# 02_-_TRICOLOR_LEDS.net
KiCad netlist of a schematic drawn in Altium Designer
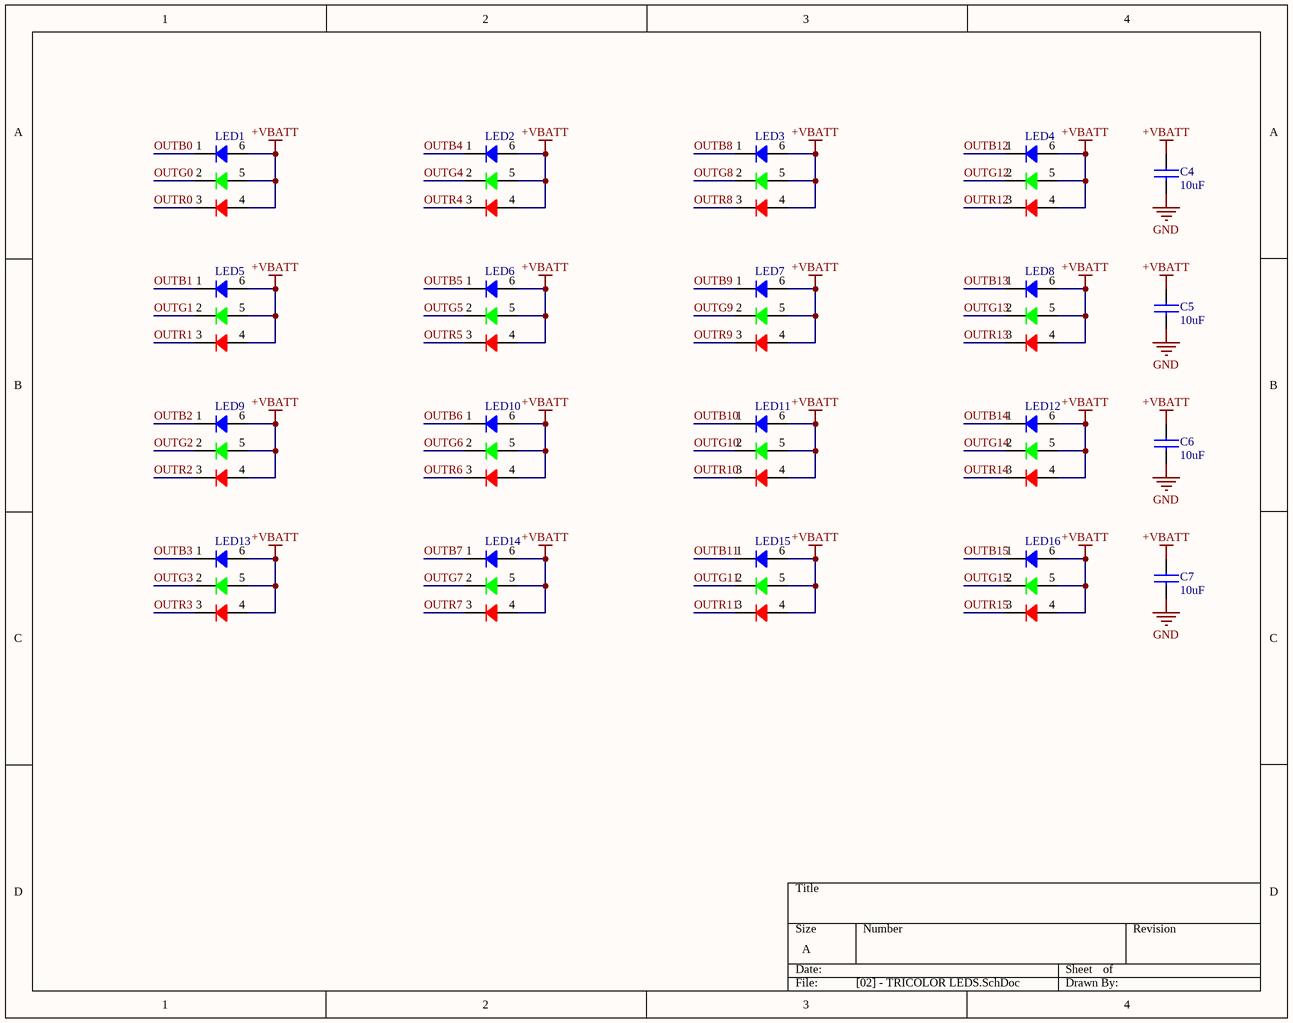
[diagram p0: [02] - TRICOLOR LEDS.SchDoc]

(export (version "E")
  (design (tool "Eeschema 10.0.6"))
  (components
    (comp (ref "C4")
      (value "10uF")
      (footprint "C0603")
      (description "Cap Ceramic 10uF 10V X5R 10% SMD 0603 85C Paper T/R")
      (fields (field (name "MANUFACTURER") "Murata") (field (name "TOLERANCE") "10%"))
      (libsource (lib "Moon_Lamp_LED_Driver") (part "GRM188R61A106KE69D"))
    )
    (comp (ref "C5")
      (value "10uF")
      (footprint "C0603")
      (description "Cap Ceramic 10uF 10V X5R 10% SMD 0603 85C Paper T/R")
      (fields (field (name "MANUFACTURER") "Murata") (field (name "TOLERANCE") "10%"))
      (libsource (lib "Moon_Lamp_LED_Driver") (part "GRM188R61A106KE69D"))
    )
    (comp (ref "C6")
      (value "10uF")
      (footprint "C0603")
      (description "Cap Ceramic 10uF 10V X5R 10% SMD 0603 85C Paper T/R")
      (fields (field (name "MANUFACTURER") "Murata") (field (name "TOLERANCE") "10%"))
      (libsource (lib "Moon_Lamp_LED_Driver") (part "GRM188R61A106KE69D"))
    )
    (comp (ref "C7")
      (value "10uF")
      (footprint "C0603")
      (description "Cap Ceramic 10uF 10V X5R 10% SMD 0603 85C Paper T/R")
      (fields (field (name "MANUFACTURER") "Murata") (field (name "TOLERANCE") "10%"))
      (libsource (lib "Moon_Lamp_LED_Driver") (part "GRM188R61A106KE69D"))
    )
    (comp (ref "LED1")
      (value "SLV6A-FKB-CK1P1G1BB7R3R3")
      (footprint "CREE SLV6A-FKB")
      (description "LED RGB 6PLCC SMD")
      (fields (field (name "MANUFACTURER") "Cree"))
      (libsource (lib "Moon_Lamp_LED_Driver") (part "SLV6A-FKB-CK1P1G1BB7R3R3"))
    )
    (comp (ref "LED2")
      (value "SLV6A-FKB-CK1P1G1BB7R3R3")
      (footprint "CREE SLV6A-FKB")
      (description "LED RGB 6PLCC SMD")
      (fields (field (name "MANUFACTURER") "Cree"))
      (libsource (lib "Moon_Lamp_LED_Driver") (part "SLV6A-FKB-CK1P1G1BB7R3R3"))
    )
    (comp (ref "LED3")
      (value "SLV6A-FKB-CK1P1G1BB7R3R3")
      (footprint "CREE SLV6A-FKB")
      (description "LED RGB 6PLCC SMD")
      (fields (field (name "MANUFACTURER") "Cree"))
      (libsource (lib "Moon_Lamp_LED_Driver") (part "SLV6A-FKB-CK1P1G1BB7R3R3"))
    )
    (comp (ref "LED4")
      (value "SLV6A-FKB-CK1P1G1BB7R3R3")
      (footprint "CREE SLV6A-FKB")
      (description "LED RGB 6PLCC SMD")
      (fields (field (name "MANUFACTURER") "Cree"))
      (libsource (lib "Moon_Lamp_LED_Driver") (part "SLV6A-FKB-CK1P1G1BB7R3R3"))
    )
    (comp (ref "LED5")
      (value "SLV6A-FKB-CK1P1G1BB7R3R3")
      (footprint "CREE SLV6A-FKB")
      (description "LED RGB 6PLCC SMD")
      (fields (field (name "MANUFACTURER") "Cree"))
      (libsource (lib "Moon_Lamp_LED_Driver") (part "SLV6A-FKB-CK1P1G1BB7R3R3"))
    )
    (comp (ref "LED6")
      (value "SLV6A-FKB-CK1P1G1BB7R3R3")
      (footprint "CREE SLV6A-FKB")
      (description "LED RGB 6PLCC SMD")
      (fields (field (name "MANUFACTURER") "Cree"))
      (libsource (lib "Moon_Lamp_LED_Driver") (part "SLV6A-FKB-CK1P1G1BB7R3R3"))
    )
    (comp (ref "LED7")
      (value "SLV6A-FKB-CK1P1G1BB7R3R3")
      (footprint "CREE SLV6A-FKB")
      (description "LED RGB 6PLCC SMD")
      (fields (field (name "MANUFACTURER") "Cree"))
      (libsource (lib "Moon_Lamp_LED_Driver") (part "SLV6A-FKB-CK1P1G1BB7R3R3"))
    )
    (comp (ref "LED8")
      (value "SLV6A-FKB-CK1P1G1BB7R3R3")
      (footprint "CREE SLV6A-FKB")
      (description "LED RGB 6PLCC SMD")
      (fields (field (name "MANUFACTURER") "Cree"))
      (libsource (lib "Moon_Lamp_LED_Driver") (part "SLV6A-FKB-CK1P1G1BB7R3R3"))
    )
    (comp (ref "LED9")
      (value "SLV6A-FKB-CK1P1G1BB7R3R3")
      (footprint "CREE SLV6A-FKB")
      (description "LED RGB 6PLCC SMD")
      (fields (field (name "MANUFACTURER") "Cree"))
      (libsource (lib "Moon_Lamp_LED_Driver") (part "SLV6A-FKB-CK1P1G1BB7R3R3"))
    )
    (comp (ref "LED10")
      (value "SLV6A-FKB-CK1P1G1BB7R3R3")
      (footprint "CREE SLV6A-FKB")
      (description "LED RGB 6PLCC SMD")
      (fields (field (name "MANUFACTURER") "Cree"))
      (libsource (lib "Moon_Lamp_LED_Driver") (part "SLV6A-FKB-CK1P1G1BB7R3R3"))
    )
    (comp (ref "LED11")
      (value "SLV6A-FKB-CK1P1G1BB7R3R3")
      (footprint "CREE SLV6A-FKB")
      (description "LED RGB 6PLCC SMD")
      (fields (field (name "MANUFACTURER") "Cree"))
      (libsource (lib "Moon_Lamp_LED_Driver") (part "SLV6A-FKB-CK1P1G1BB7R3R3"))
    )
    (comp (ref "LED12")
      (value "SLV6A-FKB-CK1P1G1BB7R3R3")
      (footprint "CREE SLV6A-FKB")
      (description "LED RGB 6PLCC SMD")
      (fields (field (name "MANUFACTURER") "Cree"))
      (libsource (lib "Moon_Lamp_LED_Driver") (part "SLV6A-FKB-CK1P1G1BB7R3R3"))
    )
    (comp (ref "LED13")
      (value "SLV6A-FKB-CK1P1G1BB7R3R3")
      (footprint "CREE SLV6A-FKB")
      (description "LED RGB 6PLCC SMD")
      (fields (field (name "MANUFACTURER") "Cree"))
      (libsource (lib "Moon_Lamp_LED_Driver") (part "SLV6A-FKB-CK1P1G1BB7R3R3"))
    )
    (comp (ref "LED14")
      (value "SLV6A-FKB-CK1P1G1BB7R3R3")
      (footprint "CREE SLV6A-FKB")
      (description "LED RGB 6PLCC SMD")
      (fields (field (name "MANUFACTURER") "Cree"))
      (libsource (lib "Moon_Lamp_LED_Driver") (part "SLV6A-FKB-CK1P1G1BB7R3R3"))
    )
    (comp (ref "LED15")
      (value "SLV6A-FKB-CK1P1G1BB7R3R3")
      (footprint "CREE SLV6A-FKB")
      (description "LED RGB 6PLCC SMD")
      (fields (field (name "MANUFACTURER") "Cree"))
      (libsource (lib "Moon_Lamp_LED_Driver") (part "SLV6A-FKB-CK1P1G1BB7R3R3"))
    )
    (comp (ref "LED16")
      (value "SLV6A-FKB-CK1P1G1BB7R3R3")
      (footprint "CREE SLV6A-FKB")
      (description "LED RGB 6PLCC SMD")
      (fields (field (name "MANUFACTURER") "Cree"))
      (libsource (lib "Moon_Lamp_LED_Driver") (part "SLV6A-FKB-CK1P1G1BB7R3R3"))
    )
  )
  (nets
    (net (code "1") (name "+VBATT") (class "Default")
      (node (ref "C4") (pin "1") (pinfunction "1_1") (pintype "passive"))
      (node (ref "C5") (pin "1") (pinfunction "1_1") (pintype "passive"))
      (node (ref "C6") (pin "1") (pinfunction "1_1") (pintype "passive"))
      (node (ref "C7") (pin "1") (pinfunction "1_1") (pintype "passive"))
      (node (ref "LED1") (pin "4") (pinfunction "4_4") (pintype "passive"))
      (node (ref "LED1") (pin "5") (pinfunction "5_5") (pintype "passive"))
      (node (ref "LED1") (pin "6") (pinfunction "6_6") (pintype "passive"))
      (node (ref "LED10") (pin "4") (pinfunction "4_4") (pintype "passive"))
      (node (ref "LED10") (pin "5") (pinfunction "5_5") (pintype "passive"))
      (node (ref "LED10") (pin "6") (pinfunction "6_6") (pintype "passive"))
      (node (ref "LED11") (pin "4") (pinfunction "4_4") (pintype "passive"))
      (node (ref "LED11") (pin "5") (pinfunction "5_5") (pintype "passive"))
      (node (ref "LED11") (pin "6") (pinfunction "6_6") (pintype "passive"))
      (node (ref "LED12") (pin "4") (pinfunction "4_4") (pintype "passive"))
      (node (ref "LED12") (pin "5") (pinfunction "5_5") (pintype "passive"))
      (node (ref "LED12") (pin "6") (pinfunction "6_6") (pintype "passive"))
      (node (ref "LED13") (pin "4") (pinfunction "4_4") (pintype "passive"))
      (node (ref "LED13") (pin "5") (pinfunction "5_5") (pintype "passive"))
      (node (ref "LED13") (pin "6") (pinfunction "6_6") (pintype "passive"))
      (node (ref "LED14") (pin "4") (pinfunction "4_4") (pintype "passive"))
      (node (ref "LED14") (pin "5") (pinfunction "5_5") (pintype "passive"))
      (node (ref "LED14") (pin "6") (pinfunction "6_6") (pintype "passive"))
      (node (ref "LED15") (pin "4") (pinfunction "4_4") (pintype "passive"))
      (node (ref "LED15") (pin "5") (pinfunction "5_5") (pintype "passive"))
      (node (ref "LED15") (pin "6") (pinfunction "6_6") (pintype "passive"))
      (node (ref "LED16") (pin "4") (pinfunction "4_4") (pintype "passive"))
      (node (ref "LED16") (pin "5") (pinfunction "5_5") (pintype "passive"))
      (node (ref "LED16") (pin "6") (pinfunction "6_6") (pintype "passive"))
      (node (ref "LED2") (pin "4") (pinfunction "4_4") (pintype "passive"))
      (node (ref "LED2") (pin "5") (pinfunction "5_5") (pintype "passive"))
      (node (ref "LED2") (pin "6") (pinfunction "6_6") (pintype "passive"))
      (node (ref "LED3") (pin "4") (pinfunction "4_4") (pintype "passive"))
      (node (ref "LED3") (pin "5") (pinfunction "5_5") (pintype "passive"))
      (node (ref "LED3") (pin "6") (pinfunction "6_6") (pintype "passive"))
      (node (ref "LED4") (pin "4") (pinfunction "4_4") (pintype "passive"))
      (node (ref "LED4") (pin "5") (pinfunction "5_5") (pintype "passive"))
      (node (ref "LED4") (pin "6") (pinfunction "6_6") (pintype "passive"))
      (node (ref "LED5") (pin "4") (pinfunction "4_4") (pintype "passive"))
      (node (ref "LED5") (pin "5") (pinfunction "5_5") (pintype "passive"))
      (node (ref "LED5") (pin "6") (pinfunction "6_6") (pintype "passive"))
      (node (ref "LED6") (pin "4") (pinfunction "4_4") (pintype "passive"))
      (node (ref "LED6") (pin "5") (pinfunction "5_5") (pintype "passive"))
      (node (ref "LED6") (pin "6") (pinfunction "6_6") (pintype "passive"))
      (node (ref "LED7") (pin "4") (pinfunction "4_4") (pintype "passive"))
      (node (ref "LED7") (pin "5") (pinfunction "5_5") (pintype "passive"))
      (node (ref "LED7") (pin "6") (pinfunction "6_6") (pintype "passive"))
      (node (ref "LED8") (pin "4") (pinfunction "4_4") (pintype "passive"))
      (node (ref "LED8") (pin "5") (pinfunction "5_5") (pintype "passive"))
      (node (ref "LED8") (pin "6") (pinfunction "6_6") (pintype "passive"))
      (node (ref "LED9") (pin "4") (pinfunction "4_4") (pintype "passive"))
      (node (ref "LED9") (pin "5") (pinfunction "5_5") (pintype "passive"))
      (node (ref "LED9") (pin "6") (pinfunction "6_6") (pintype "passive"))
    )
    (net (code "2") (name "/OUTB0") (class "Default")
      (node (ref "LED1") (pin "1") (pinfunction "1_1") (pintype "passive"))
    )
    (net (code "3") (name "/OUTB1") (class "Default")
      (node (ref "LED5") (pin "1") (pinfunction "1_1") (pintype "passive"))
    )
    (net (code "4") (name "/OUTB2") (class "Default")
      (node (ref "LED9") (pin "1") (pinfunction "1_1") (pintype "passive"))
    )
    (net (code "5") (name "/OUTB3") (class "Default")
      (node (ref "LED13") (pin "1") (pinfunction "1_1") (pintype "passive"))
    )
    (net (code "6") (name "/OUTB4") (class "Default")
      (node (ref "LED2") (pin "1") (pinfunction "1_1") (pintype "passive"))
    )
    (net (code "7") (name "/OUTB5") (class "Default")
      (node (ref "LED6") (pin "1") (pinfunction "1_1") (pintype "passive"))
    )
    (net (code "8") (name "/OUTB6") (class "Default")
      (node (ref "LED10") (pin "1") (pinfunction "1_1") (pintype "passive"))
    )
    (net (code "9") (name "/OUTB7") (class "Default")
      (node (ref "LED14") (pin "1") (pinfunction "1_1") (pintype "passive"))
    )
    (net (code "10") (name "/OUTB8") (class "Default")
      (node (ref "LED3") (pin "1") (pinfunction "1_1") (pintype "passive"))
    )
    (net (code "11") (name "/OUTB9") (class "Default")
      (node (ref "LED7") (pin "1") (pinfunction "1_1") (pintype "passive"))
    )
    (net (code "12") (name "/OUTB10") (class "Default")
      (node (ref "LED11") (pin "1") (pinfunction "1_1") (pintype "passive"))
    )
    (net (code "13") (name "/OUTB11") (class "Default")
      (node (ref "LED15") (pin "1") (pinfunction "1_1") (pintype "passive"))
    )
    (net (code "14") (name "/OUTB12") (class "Default")
      (node (ref "LED4") (pin "1") (pinfunction "1_1") (pintype "passive"))
    )
    (net (code "15") (name "/OUTB13") (class "Default")
      (node (ref "LED8") (pin "1") (pinfunction "1_1") (pintype "passive"))
    )
    (net (code "16") (name "/OUTB14") (class "Default")
      (node (ref "LED12") (pin "1") (pinfunction "1_1") (pintype "passive"))
    )
    (net (code "17") (name "/OUTB15") (class "Default")
      (node (ref "LED16") (pin "1") (pinfunction "1_1") (pintype "passive"))
    )
    (net (code "18") (name "/OUTG0") (class "Default")
      (node (ref "LED1") (pin "2") (pinfunction "2_2") (pintype "passive"))
    )
    (net (code "19") (name "/OUTG1") (class "Default")
      (node (ref "LED5") (pin "2") (pinfunction "2_2") (pintype "passive"))
    )
    (net (code "20") (name "/OUTG2") (class "Default")
      (node (ref "LED9") (pin "2") (pinfunction "2_2") (pintype "passive"))
    )
    (net (code "21") (name "/OUTG3") (class "Default")
      (node (ref "LED13") (pin "2") (pinfunction "2_2") (pintype "passive"))
    )
    (net (code "22") (name "/OUTG4") (class "Default")
      (node (ref "LED2") (pin "2") (pinfunction "2_2") (pintype "passive"))
    )
    (net (code "23") (name "/OUTG5") (class "Default")
      (node (ref "LED6") (pin "2") (pinfunction "2_2") (pintype "passive"))
    )
    (net (code "24") (name "/OUTG6") (class "Default")
      (node (ref "LED10") (pin "2") (pinfunction "2_2") (pintype "passive"))
    )
    (net (code "25") (name "/OUTG7") (class "Default")
      (node (ref "LED14") (pin "2") (pinfunction "2_2") (pintype "passive"))
    )
    (net (code "26") (name "/OUTG8") (class "Default")
      (node (ref "LED3") (pin "2") (pinfunction "2_2") (pintype "passive"))
    )
    (net (code "27") (name "/OUTG9") (class "Default")
      (node (ref "LED7") (pin "2") (pinfunction "2_2") (pintype "passive"))
    )
    (net (code "28") (name "/OUTG10") (class "Default")
      (node (ref "LED11") (pin "2") (pinfunction "2_2") (pintype "passive"))
    )
    (net (code "29") (name "/OUTG11") (class "Default")
      (node (ref "LED15") (pin "2") (pinfunction "2_2") (pintype "passive"))
    )
    (net (code "30") (name "/OUTG12") (class "Default")
      (node (ref "LED4") (pin "2") (pinfunction "2_2") (pintype "passive"))
    )
    (net (code "31") (name "/OUTG13") (class "Default")
      (node (ref "LED8") (pin "2") (pinfunction "2_2") (pintype "passive"))
    )
    (net (code "32") (name "/OUTG14") (class "Default")
      (node (ref "LED12") (pin "2") (pinfunction "2_2") (pintype "passive"))
    )
    (net (code "33") (name "/OUTG15") (class "Default")
      (node (ref "LED16") (pin "2") (pinfunction "2_2") (pintype "passive"))
    )
    (net (code "34") (name "/OUTR0") (class "Default")
      (node (ref "LED1") (pin "3") (pinfunction "2_3") (pintype "passive"))
    )
    (net (code "35") (name "/OUTR1") (class "Default")
      (node (ref "LED5") (pin "3") (pinfunction "2_3") (pintype "passive"))
    )
    (net (code "36") (name "/OUTR2") (class "Default")
      (node (ref "LED9") (pin "3") (pinfunction "2_3") (pintype "passive"))
    )
    (net (code "37") (name "/OUTR3") (class "Default")
      (node (ref "LED13") (pin "3") (pinfunction "2_3") (pintype "passive"))
    )
    (net (code "38") (name "/OUTR4") (class "Default")
      (node (ref "LED2") (pin "3") (pinfunction "2_3") (pintype "passive"))
    )
    (net (code "39") (name "/OUTR5") (class "Default")
      (node (ref "LED6") (pin "3") (pinfunction "2_3") (pintype "passive"))
    )
    (net (code "40") (name "/OUTR6") (class "Default")
      (node (ref "LED10") (pin "3") (pinfunction "2_3") (pintype "passive"))
    )
    (net (code "41") (name "/OUTR7") (class "Default")
      (node (ref "LED14") (pin "3") (pinfunction "2_3") (pintype "passive"))
    )
    (net (code "42") (name "/OUTR8") (class "Default")
      (node (ref "LED3") (pin "3") (pinfunction "2_3") (pintype "passive"))
    )
    (net (code "43") (name "/OUTR9") (class "Default")
      (node (ref "LED7") (pin "3") (pinfunction "2_3") (pintype "passive"))
    )
    (net (code "44") (name "/OUTR10") (class "Default")
      (node (ref "LED11") (pin "3") (pinfunction "2_3") (pintype "passive"))
    )
    (net (code "45") (name "/OUTR11") (class "Default")
      (node (ref "LED15") (pin "3") (pinfunction "2_3") (pintype "passive"))
    )
    (net (code "46") (name "/OUTR12") (class "Default")
      (node (ref "LED4") (pin "3") (pinfunction "2_3") (pintype "passive"))
    )
    (net (code "47") (name "/OUTR13") (class "Default")
      (node (ref "LED8") (pin "3") (pinfunction "2_3") (pintype "passive"))
    )
    (net (code "48") (name "/OUTR14") (class "Default")
      (node (ref "LED12") (pin "3") (pinfunction "2_3") (pintype "passive"))
    )
    (net (code "49") (name "/OUTR15") (class "Default")
      (node (ref "LED16") (pin "3") (pinfunction "2_3") (pintype "passive"))
    )
    (net (code "50") (name "GND") (class "Default")
      (node (ref "C4") (pin "2") (pinfunction "2_2") (pintype "passive"))
      (node (ref "C5") (pin "2") (pinfunction "2_2") (pintype "passive"))
      (node (ref "C6") (pin "2") (pinfunction "2_2") (pintype "passive"))
      (node (ref "C7") (pin "2") (pinfunction "2_2") (pintype "passive"))
    )
  )
)
